# IR2101.net
KiCad netlist of a schematic drawn in Altium Designer
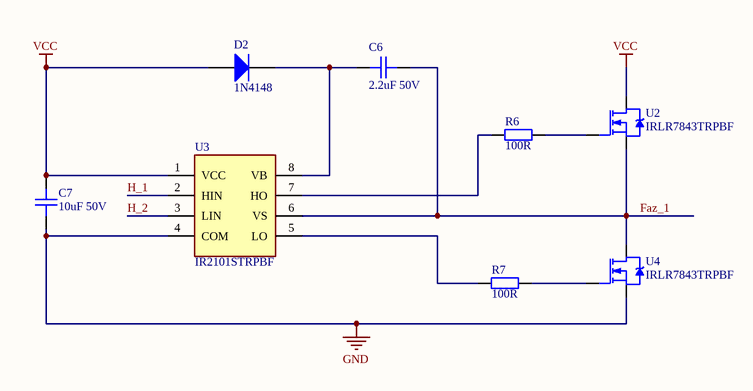
[diagram p0: IR2101.SchDoc]

(export (version "E")
  (design (tool "Eeschema 10.0.6"))
  (components
    (comp (ref "C6")
      (value "CAP CER 2.2UF 50V X5R 1206")
      (footprint "CAP 1206/3216")
      (description "2.2µF ±10% 50V Ceramic Capacitor X5R 1206 (3216 Metric)")
      (fields (field (name "DEGER") "2.2uF 50V"))
      (libsource (lib "PROJE") (part "2.2uF 50V 1206"))
    )
    (comp (ref "C7")
      (value "CAP CER 10UF 50V X5R 1206")
      (footprint "CAP 1206/3216")
      (description "10µF ±10% 50V Ceramic Capacitor X5R 1206 (3216 Metric)")
      (fields (field (name "DEGER") "10uF 50V"))
      (libsource (lib "PROJE") (part "10uF 50V 1206"))
    )
    (comp (ref "D2")
      (value "1N4148 Diyot")
      (footprint "SOD-123")
      (description "DIODE GEN PURP 100V 150MA SOD123")
      (fields (field (name "DEGER") "1N4148"))
      (libsource (lib "PROJE") (part "1N4148"))
    )
    (comp (ref "R6")
      (value "RES SMD 100 OHM 1% 1/8W 0805")
      (footprint "RES_0805")
      (description "100 Ohms ±1% 0.125W, 1/8W Chip Resistor 0805 (2012 Metric) Moisture Resistant Thick Film")
      (fields (field (name "DEGER") "100R"))
      (libsource (lib "PROJE") (part "100R 0805"))
    )
    (comp (ref "R7")
      (value "RES SMD 100 OHM 1% 1/8W 0805")
      (footprint "RES_0805")
      (description "100 Ohms ±1% 0.125W, 1/8W Chip Resistor 0805 (2012 Metric) Moisture Resistant Thick Film")
      (fields (field (name "DEGER") "100R"))
      (libsource (lib "PROJE") (part "100R 0805"))
    )
    (comp (ref "U2")
      (value "MOSFET N-CH 30V 161A DPAK")
      (footprint "DPAK")
      (description "N-Channel 30V 161A (Tc) 140W (Tc) Surface Mount D-Pak")
      (fields (field (name "DEGER") "IRLR7843TRPBF"))
      (libsource (lib "PROJE") (part "IRLR7843"))
    )
    (comp (ref "U3")
      (value "IC GATE DRVR HALF-BRIDGE 8SOIC")
      (footprint "SOIC8")
      (description "Half-Bridge Gate Driver IC Non-Inverting 8-SOIC")
      (fields (field (name "DEGER") "IR2101STRPBF"))
      (libsource (lib "PROJE") (part "IR2101"))
    )
    (comp (ref "U4")
      (value "MOSFET N-CH 30V 161A DPAK")
      (footprint "DPAK")
      (description "N-Channel 30V 161A (Tc) 140W (Tc) Surface Mount D-Pak")
      (fields (field (name "DEGER") "IRLR7843TRPBF"))
      (libsource (lib "PROJE") (part "IRLR7843"))
    )
  )
  (nets
    (net (code "1") (name "/Faz_1") (class "Default")
      (node (ref "C6") (pin "1") (pinfunction "1_1") (pintype "passive"))
      (node (ref "U2") (pin "3") (pinfunction "S_3") (pintype "passive"))
      (node (ref "U3") (pin "6") (pinfunction "VS_6") (pintype "passive"))
      (node (ref "U4") (pin "4") (pinfunction "D_4") (pintype "passive"))
    )
    (net (code "2") (name "/H_1") (class "Default")
      (node (ref "U3") (pin "2") (pinfunction "HIN_2") (pintype "passive"))
    )
    (net (code "3") (name "/H_2") (class "Default")
      (node (ref "U3") (pin "3") (pinfunction "LIN_3") (pintype "passive"))
    )
    (net (code "4") (name "GND") (class "Default")
      (node (ref "C7") (pin "1") (pinfunction "1_1") (pintype "passive"))
      (node (ref "U3") (pin "4") (pinfunction "COM_4") (pintype "passive"))
      (node (ref "U4") (pin "3") (pinfunction "S_3") (pintype "passive"))
    )
    (net (code "5") (name "Net-(D2-K)") (class "Default")
      (node (ref "C6") (pin "2") (pinfunction "2_2") (pintype "passive"))
      (node (ref "D2") (pin "2") (pinfunction "K_2") (pintype "passive"))
      (node (ref "U3") (pin "8") (pinfunction "VB_8") (pintype "passive"))
    )
    (net (code "6") (name "Net-(U2-G)") (class "Default")
      (node (ref "R6") (pin "2") (pinfunction "2_2") (pintype "passive"))
      (node (ref "U2") (pin "1") (pinfunction "G_1") (pintype "passive"))
    )
    (net (code "7") (name "Net-(U3-HO)") (class "Default")
      (node (ref "R6") (pin "1") (pinfunction "1_1") (pintype "passive"))
      (node (ref "U3") (pin "7") (pinfunction "HO_7") (pintype "passive"))
    )
    (net (code "8") (name "Net-(U3-LO)") (class "Default")
      (node (ref "R7") (pin "1") (pinfunction "1_1") (pintype "passive"))
      (node (ref "U3") (pin "5") (pinfunction "LO_5") (pintype "passive"))
    )
    (net (code "9") (name "Net-(U4-G)") (class "Default")
      (node (ref "R7") (pin "2") (pinfunction "2_2") (pintype "passive"))
      (node (ref "U4") (pin "1") (pinfunction "G_1") (pintype "passive"))
    )
    (net (code "10") (name "VCC") (class "Default")
      (node (ref "C7") (pin "2") (pinfunction "2_2") (pintype "passive"))
      (node (ref "D2") (pin "1") (pinfunction "A_1") (pintype "passive"))
      (node (ref "U2") (pin "4") (pinfunction "D_4") (pintype "passive"))
      (node (ref "U3") (pin "1") (pinfunction "VCC_1") (pintype "passive"))
    )
  )
)
